# V1_LM339.net
KiCad netlist of a schematic drawn in EAGLE
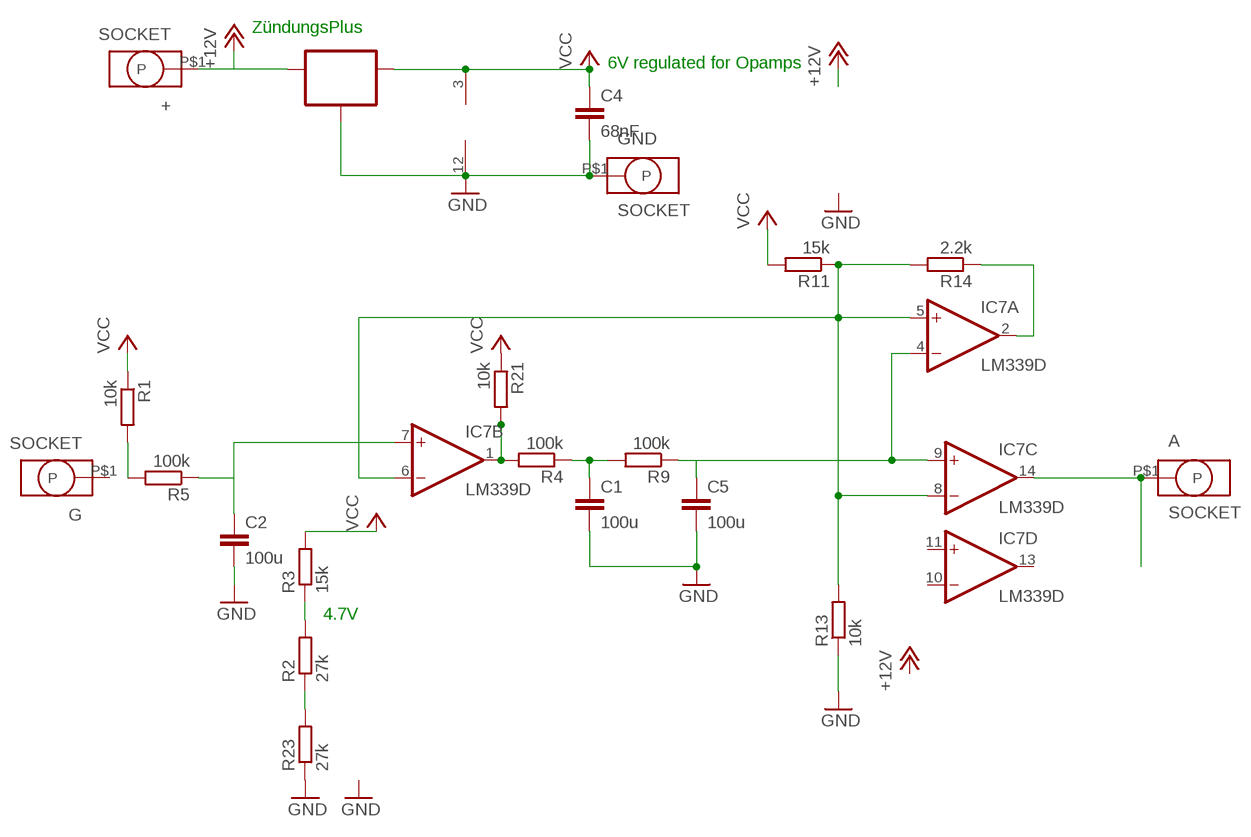
[diagram p0: schematic, sheet 1]

(export (version "E")
  (design (tool "Eeschema 10.0.6"))
  (components
    (comp (ref "+")
      (value "SOCKET")
      (footprint "eagle-import:ID2.5MM")
      (libsource (lib "eagle-import") (part "SOCKET"))
    )
    (comp (ref "A")
      (value "SOCKET")
      (footprint "eagle-import:ID2.5MM")
      (libsource (lib "eagle-import") (part "SOCKET"))
    )
    (comp (ref "C1")
      (value "100u")
      (footprint "eagle-import:C1206K")
      (libsource (lib "eagle-import") (part "C-EUC1206K"))
    )
    (comp (ref "C2")
      (value "100u")
      (footprint "eagle-import:C1206K")
      (libsource (lib "eagle-import") (part "C-EUC1206K"))
    )
    (comp (ref "C4")
      (value "68nF")
      (footprint "eagle-import:C1206K")
      (libsource (lib "eagle-import") (part "C-EUC1206K"))
    )
    (comp (ref "C5")
      (value "100u")
      (footprint "eagle-import:C1206K")
      (libsource (lib "eagle-import") (part "C-EUC1206K"))
    )
    (comp (ref "G")
      (value "SOCKET")
      (footprint "eagle-import:ID2.5MM")
      (libsource (lib "eagle-import") (part "SOCKET"))
    )
    (comp (ref "GND")
      (value "SOCKET")
      (footprint "eagle-import:ID2.5MM")
      (libsource (lib "eagle-import") (part "SOCKET"))
    )
    (comp (ref "IC2")
      (value "78LXXSOT89_ROUND")
      (footprint "eagle-import:SOT89_ROUND")
      (libsource (lib "eagle-import") (part "78LXXSOT89_ROUND"))
    )
    (comp (ref "IC7")
      (value "LM339D")
      (footprint "eagle-import:SO14")
      (libsource (lib "eagle-import") (part "LM339D"))
    )
    (comp (ref "R1")
      (value "10k")
      (footprint "eagle-import:R0805")
      (libsource (lib "eagle-import") (part "R-EU_R0805"))
    )
    (comp (ref "R2")
      (value "27k")
      (footprint "eagle-import:R0805")
      (libsource (lib "eagle-import") (part "R-EU_R0805"))
    )
    (comp (ref "R3")
      (value "15k")
      (footprint "eagle-import:R0805")
      (libsource (lib "eagle-import") (part "R-EU_R0805"))
    )
    (comp (ref "R4")
      (value "100k")
      (footprint "eagle-import:R0805")
      (libsource (lib "eagle-import") (part "R-EU_R0805"))
    )
    (comp (ref "R5")
      (value "100k")
      (footprint "eagle-import:R0805")
      (libsource (lib "eagle-import") (part "R-EU_R0805"))
    )
    (comp (ref "R9")
      (value "100k")
      (footprint "eagle-import:R0805")
      (libsource (lib "eagle-import") (part "R-EU_R0805"))
    )
    (comp (ref "R11")
      (value "15k")
      (footprint "eagle-import:R0805")
      (libsource (lib "eagle-import") (part "R-EU_R0805"))
    )
    (comp (ref "R13")
      (value "10k")
      (footprint "eagle-import:R0805")
      (libsource (lib "eagle-import") (part "R-EU_R0805"))
    )
    (comp (ref "R14")
      (value "2.2k")
      (footprint "eagle-import:R0805")
      (libsource (lib "eagle-import") (part "R-EU_R0805"))
    )
    (comp (ref "R21")
      (value "10k")
      (footprint "eagle-import:R0805")
      (libsource (lib "eagle-import") (part "R-EU_R0805"))
    )
    (comp (ref "R23")
      (value "27k")
      (footprint "eagle-import:R0805")
      (libsource (lib "eagle-import") (part "R-EU_R0805"))
    )
  )
  (nets
    (net (code "1") (name "+12V") (class "Default")
      (node (ref "+") (pin "P$1") (pinfunction "P_P$1") (pintype "bidirectional"))
      (node (ref "IC2") (pin "3") (pinfunction "IN_3") (pintype "input"))
    )
    (net (code "2") (name "GND") (class "Default")
      (node (ref "C1") (pin "2") (pinfunction "2_2") (pintype "passive"))
      (node (ref "C2") (pin "2") (pinfunction "2_2") (pintype "passive"))
      (node (ref "C4") (pin "2") (pinfunction "2_2") (pintype "passive"))
      (node (ref "C5") (pin "2") (pinfunction "2_2") (pintype "passive"))
      (node (ref "GND") (pin "P$1") (pinfunction "P_P$1") (pintype "bidirectional"))
      (node (ref "IC2") (pin "2") (pinfunction "GND_2") (pintype "input"))
      (node (ref "IC2") (pin "2@1") (pinfunction "GND_2@1") (pintype "input"))
      (node (ref "IC7") (pin "12") (pinfunction "GND_12") (pintype "power_in"))
      (node (ref "R13") (pin "1") (pinfunction "1_1") (pintype "passive"))
      (node (ref "R23") (pin "1") (pinfunction "1_1") (pintype "passive"))
    )
    (net (code "3") (name "Net-(A-P)") (class "Default")
      (node (ref "A") (pin "P$1") (pinfunction "P_P$1") (pintype "bidirectional"))
      (node (ref "IC7") (pin "14") (pinfunction "OUT_14") (pintype "open_collector"))
    )
    (net (code "4") (name "Net-(C1-Pad1)") (class "Default")
      (node (ref "C1") (pin "1") (pinfunction "1_1") (pintype "passive"))
      (node (ref "R4") (pin "1") (pinfunction "1_1") (pintype "passive"))
      (node (ref "R9") (pin "2") (pinfunction "2_2") (pintype "passive"))
    )
    (net (code "5") (name "Net-(IC7A-+IN)") (class "Default")
      (node (ref "IC7") (pin "5") (pinfunction "+IN_5") (pintype "input"))
      (node (ref "IC7") (pin "6") (pinfunction "-IN_6") (pintype "input"))
      (node (ref "IC7") (pin "8") (pinfunction "-IN_8") (pintype "input"))
      (node (ref "R11") (pin "1") (pinfunction "1_1") (pintype "passive"))
      (node (ref "R13") (pin "2") (pinfunction "2_2") (pintype "passive"))
      (node (ref "R14") (pin "2") (pinfunction "2_2") (pintype "passive"))
    )
    (net (code "6") (name "Net-(IC7A--IN)") (class "Default")
      (node (ref "C5") (pin "1") (pinfunction "1_1") (pintype "passive"))
      (node (ref "IC7") (pin "4") (pinfunction "-IN_4") (pintype "input"))
      (node (ref "IC7") (pin "9") (pinfunction "+IN_9") (pintype "input"))
      (node (ref "R9") (pin "1") (pinfunction "1_1") (pintype "passive"))
    )
    (net (code "7") (name "Net-(IC7A-OUT)") (class "Default")
      (node (ref "IC7") (pin "2") (pinfunction "OUT_2") (pintype "open_collector"))
      (node (ref "R14") (pin "1") (pinfunction "1_1") (pintype "passive"))
    )
    (net (code "8") (name "Net-(IC7B-+IN)") (class "Default")
      (node (ref "C2") (pin "1") (pinfunction "1_1") (pintype "passive"))
      (node (ref "IC7") (pin "7") (pinfunction "+IN_7") (pintype "input"))
      (node (ref "R5") (pin "1") (pinfunction "1_1") (pintype "passive"))
    )
    (net (code "9") (name "Net-(IC7B-OUT)") (class "Default")
      (node (ref "IC7") (pin "1") (pinfunction "OUT_1") (pintype "open_collector"))
      (node (ref "R21") (pin "2") (pinfunction "2_2") (pintype "passive"))
      (node (ref "R4") (pin "2") (pinfunction "2_2") (pintype "passive"))
    )
    (net (code "10") (name "Net-(R1-Pad2)") (class "Default")
      (node (ref "R1") (pin "2") (pinfunction "2_2") (pintype "passive"))
      (node (ref "R5") (pin "2") (pinfunction "2_2") (pintype "passive"))
    )
    (net (code "11") (name "Net-(R2-Pad1)") (class "Default")
      (node (ref "R2") (pin "1") (pinfunction "1_1") (pintype "passive"))
      (node (ref "R23") (pin "2") (pinfunction "2_2") (pintype "passive"))
    )
    (net (code "12") (name "Net-(R2-Pad2)") (class "Default")
      (node (ref "R2") (pin "2") (pinfunction "2_2") (pintype "passive"))
      (node (ref "R3") (pin "1") (pinfunction "1_1") (pintype "passive"))
    )
    (net (code "13") (name "VCC") (class "Default")
      (node (ref "C4") (pin "1") (pinfunction "1_1") (pintype "passive"))
      (node (ref "IC2") (pin "1") (pinfunction "OUT_1") (pintype "passive"))
      (node (ref "IC7") (pin "3") (pinfunction "V+_3") (pintype "power_in"))
      (node (ref "R1") (pin "1") (pinfunction "1_1") (pintype "passive"))
      (node (ref "R11") (pin "2") (pinfunction "2_2") (pintype "passive"))
      (node (ref "R21") (pin "1") (pinfunction "1_1") (pintype "passive"))
      (node (ref "R3") (pin "2") (pinfunction "2_2") (pintype "passive"))
    )
    (net (code "14") (name "unconnected-(G-P-PadP$1)") (class "Default")
      (node (ref "G") (pin "P$1") (pinfunction "P_P$1") (pintype "bidirectional"))
    )
    (net (code "15") (name "unconnected-(IC7D-+IN-Pad11)") (class "Default")
      (node (ref "IC7") (pin "11") (pinfunction "+IN_11") (pintype "input"))
    )
    (net (code "16") (name "unconnected-(IC7D--IN-Pad10)") (class "Default")
      (node (ref "IC7") (pin "10") (pinfunction "-IN_10") (pintype "input"))
    )
    (net (code "17") (name "unconnected-(IC7D-OUT-Pad13)") (class "Default")
      (node (ref "IC7") (pin "13") (pinfunction "OUT_13") (pintype "open_collector"))
    )
  )
)
